# Sheet1.net
KiCad netlist of a schematic drawn in Altium Designer
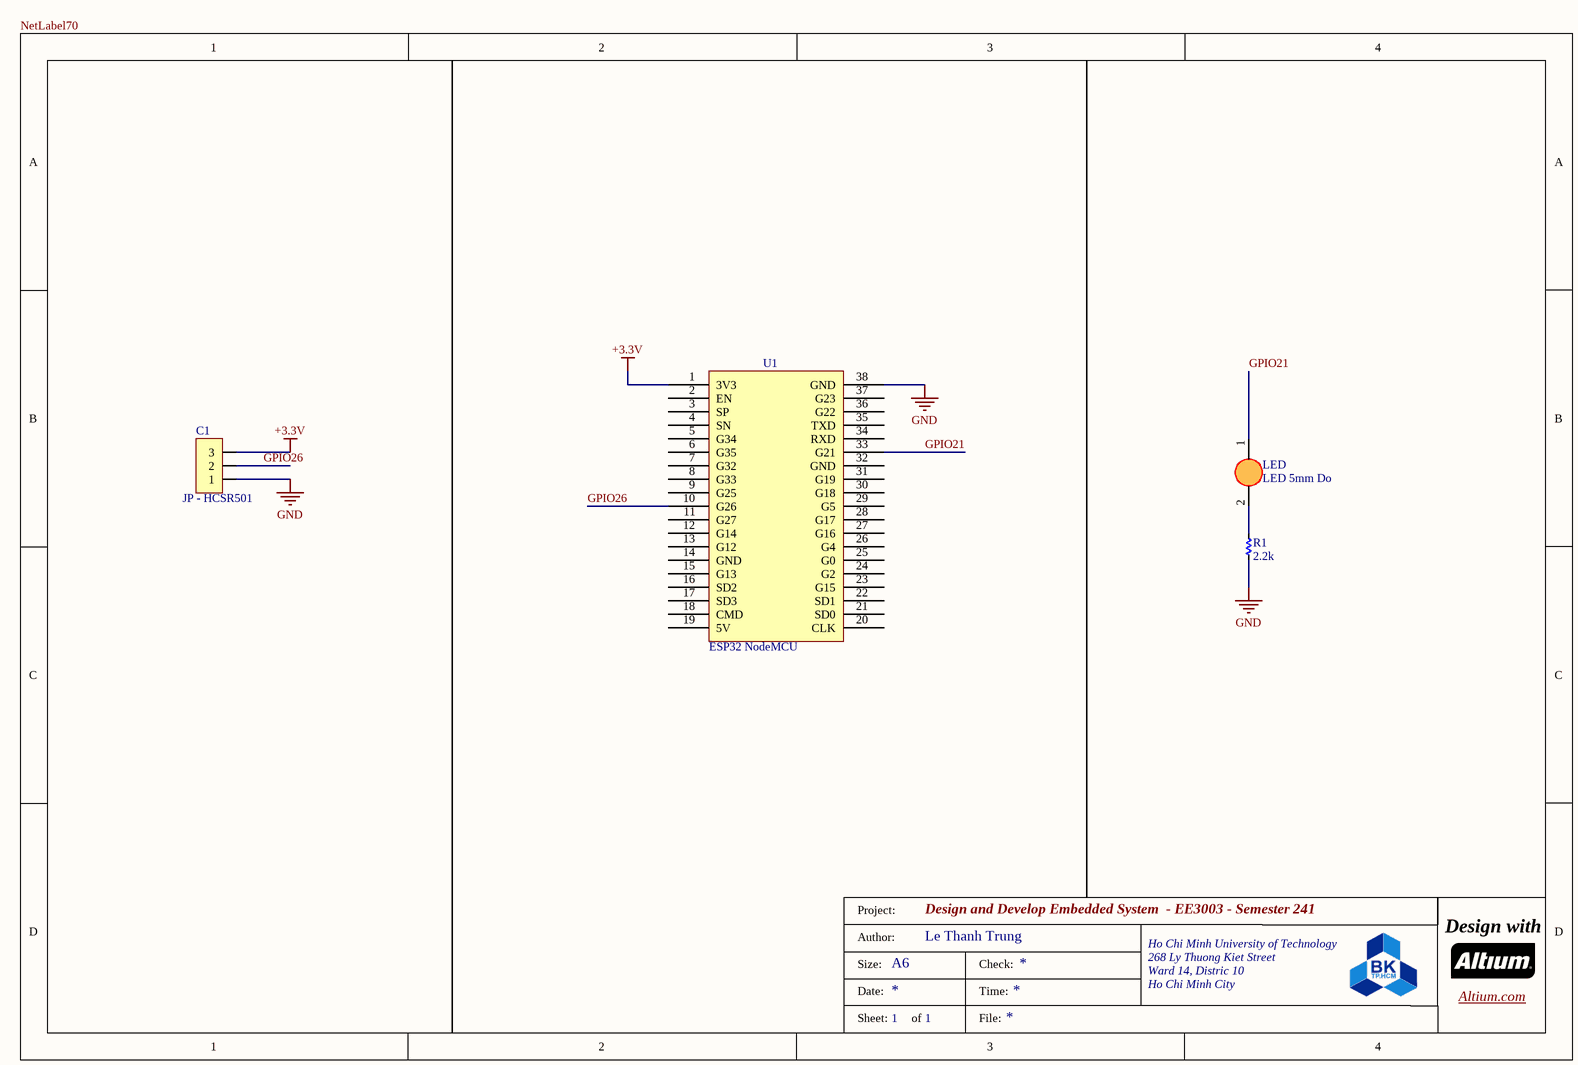
[diagram p0: Sheet1.SchDoc]

(export (version "E")
  (design (tool "Eeschema 10.0.6"))
  (components
    (comp (ref "C1")
      (value "JP - HCSR501")
      (footprint "JP3-C1T")
      (description "WR-PHD 2.54 mm Angled Socket Header")
      (fields
        (field (name "MANUFACTURER") "Würth Elektronik eiSos GmbH")
        (field (name "PARTNO") "613003143121")
        (field (name "CREATED BY") "Karrer Zheng")
      )
      (libsource (lib "KhanhBK_SCH_Library_1") (part "JP3"))
    )
    (comp (ref "LED")
      (value "LED 5mm Do")
      (footprint "LED 5mm DO")
      (description "Cắm")
      (libsource (lib "THU VIEN SCH") (part "LED 5mm Do"))
    )
    (comp (ref "R1")
      (value "2.2k")
      (footprint "RES-1W")
      (description "Res")
      (fields
        (field (name "MANUFACTURER") "Generic Components")
        (field (name "PUBLISHER") "Altium Hobart Technology Centre")
      )
      (libsource (lib "KhanhBK_SCH_Library_1") (part "Res"))
    )
    (comp (ref "U1")
      (value "ESP32 NodeMCU")
      (footprint "Nodemcu-32s")
      (description "38 pins")
      (libsource (lib "Schlib2") (part "ESP32 NodeMCU"))
    )
  )
  (nets
    (net (code "1") (name "+3.3V") (class "Default")
      (node (ref "C1") (pin "3") (pinfunction "3_3") (pintype "passive"))
      (node (ref "U1") (pin "1") (pinfunction "3V3_1") (pintype "power_in"))
    )
    (net (code "2") (name "/GPIO21") (class "Default")
      (node (ref "LED") (pin "1") (pinfunction "A_1") (pintype "passive"))
      (node (ref "U1") (pin "33") (pinfunction "G21_33") (pintype "passive"))
    )
    (net (code "3") (name "/GPIO26") (class "Default")
      (node (ref "C1") (pin "2") (pinfunction "2_2") (pintype "passive"))
      (node (ref "U1") (pin "10") (pinfunction "G26_10") (pintype "passive"))
    )
    (net (code "7") (name "GND") (class "Default")
      (node (ref "C1") (pin "1") (pinfunction "1_1") (pintype "passive"))
      (node (ref "R1") (pin "1") (pinfunction "1_1") (pintype "passive"))
      (node (ref "U1") (pin "38") (pinfunction "GND_38") (pintype "power_in"))
    )
    (net (code "8") (name "Net-(LED-K)") (class "Default")
      (node (ref "LED") (pin "2") (pinfunction "K_2") (pintype "passive"))
      (node (ref "R1") (pin "2") (pinfunction "2_2") (pintype "passive"))
    )
    (net (code "9") (name "unconnected-(U1-5V-Pad19)") (class "Default")
      (node (ref "U1") (pin "19") (pinfunction "5V_19") (pintype "power_in"))
    )
    (net (code "10") (name "unconnected-(U1-CLK-Pad20)") (class "Default")
      (node (ref "U1") (pin "20") (pinfunction "CLK_20") (pintype "passive"))
    )
    (net (code "11") (name "unconnected-(U1-CMD-Pad18)") (class "Default")
      (node (ref "U1") (pin "18") (pinfunction "CMD_18") (pintype "passive"))
    )
    (net (code "12") (name "unconnected-(U1-EN-Pad2)") (class "Default")
      (node (ref "U1") (pin "2") (pinfunction "EN_2") (pintype "passive"))
    )
    (net (code "13") (name "unconnected-(U1-G0-Pad25)") (class "Default")
      (node (ref "U1") (pin "25") (pinfunction "G0_25") (pintype "passive"))
    )
    (net (code "14") (name "unconnected-(U1-G2-Pad24)") (class "Default")
      (node (ref "U1") (pin "24") (pinfunction "G2_24") (pintype "passive"))
    )
    (net (code "15") (name "unconnected-(U1-G4-Pad26)") (class "Default")
      (node (ref "U1") (pin "26") (pinfunction "G4_26") (pintype "passive"))
    )
    (net (code "16") (name "unconnected-(U1-G5-Pad29)") (class "Default")
      (node (ref "U1") (pin "29") (pinfunction "G5_29") (pintype "passive"))
    )
    (net (code "17") (name "unconnected-(U1-G12-Pad13)") (class "Default")
      (node (ref "U1") (pin "13") (pinfunction "G12_13") (pintype "passive"))
    )
    (net (code "18") (name "unconnected-(U1-G13-Pad15)") (class "Default")
      (node (ref "U1") (pin "15") (pinfunction "G13_15") (pintype "passive"))
    )
    (net (code "19") (name "unconnected-(U1-G14-Pad12)") (class "Default")
      (node (ref "U1") (pin "12") (pinfunction "G14_12") (pintype "passive"))
    )
    (net (code "20") (name "unconnected-(U1-G15-Pad23)") (class "Default")
      (node (ref "U1") (pin "23") (pinfunction "G15_23") (pintype "passive"))
    )
    (net (code "21") (name "unconnected-(U1-G16-Pad27)") (class "Default")
      (node (ref "U1") (pin "27") (pinfunction "G16_27") (pintype "passive"))
    )
    (net (code "22") (name "unconnected-(U1-G17-Pad28)") (class "Default")
      (node (ref "U1") (pin "28") (pinfunction "G17_28") (pintype "passive"))
    )
    (net (code "23") (name "unconnected-(U1-G18-Pad30)") (class "Default")
      (node (ref "U1") (pin "30") (pinfunction "G18_30") (pintype "passive"))
    )
    (net (code "24") (name "unconnected-(U1-G19-Pad31)") (class "Default")
      (node (ref "U1") (pin "31") (pinfunction "G19_31") (pintype "passive"))
    )
    (net (code "25") (name "unconnected-(U1-G22-Pad36)") (class "Default")
      (node (ref "U1") (pin "36") (pinfunction "G22_36") (pintype "passive"))
    )
    (net (code "26") (name "unconnected-(U1-G23-Pad37)") (class "Default")
      (node (ref "U1") (pin "37") (pinfunction "G23_37") (pintype "passive"))
    )
    (net (code "27") (name "unconnected-(U1-G25-Pad9)") (class "Default")
      (node (ref "U1") (pin "9") (pinfunction "G25_9") (pintype "passive"))
    )
    (net (code "28") (name "unconnected-(U1-G27-Pad11)") (class "Default")
      (node (ref "U1") (pin "11") (pinfunction "G27_11") (pintype "passive"))
    )
    (net (code "29") (name "unconnected-(U1-G32-Pad7)") (class "Default")
      (node (ref "U1") (pin "7") (pinfunction "G32_7") (pintype "passive"))
    )
    (net (code "30") (name "unconnected-(U1-G33-Pad8)") (class "Default")
      (node (ref "U1") (pin "8") (pinfunction "G33_8") (pintype "passive"))
    )
    (net (code "31") (name "unconnected-(U1-G34-Pad5)") (class "Default")
      (node (ref "U1") (pin "5") (pinfunction "G34_5") (pintype "passive"))
    )
    (net (code "32") (name "unconnected-(U1-G35-Pad6)") (class "Default")
      (node (ref "U1") (pin "6") (pinfunction "G35_6") (pintype "passive"))
    )
    (net (code "33") (name "unconnected-(U1-GND-Pad14)") (class "Default")
      (node (ref "U1") (pin "14") (pinfunction "GND_14") (pintype "power_in"))
    )
    (net (code "34") (name "unconnected-(U1-GND-Pad32)") (class "Default")
      (node (ref "U1") (pin "32") (pinfunction "GND_32") (pintype "power_in"))
    )
    (net (code "35") (name "unconnected-(U1-RXD-Pad34)") (class "Default")
      (node (ref "U1") (pin "34") (pinfunction "RXD_34") (pintype "passive"))
    )
    (net (code "36") (name "unconnected-(U1-SD0-Pad21)") (class "Default")
      (node (ref "U1") (pin "21") (pinfunction "SD0_21") (pintype "passive"))
    )
    (net (code "37") (name "unconnected-(U1-SD1-Pad22)") (class "Default")
      (node (ref "U1") (pin "22") (pinfunction "SD1_22") (pintype "passive"))
    )
    (net (code "38") (name "unconnected-(U1-SD2-Pad16)") (class "Default")
      (node (ref "U1") (pin "16") (pinfunction "SD2_16") (pintype "passive"))
    )
    (net (code "39") (name "unconnected-(U1-SD3-Pad17)") (class "Default")
      (node (ref "U1") (pin "17") (pinfunction "SD3_17") (pintype "passive"))
    )
    (net (code "40") (name "unconnected-(U1-SN-Pad4)") (class "Default")
      (node (ref "U1") (pin "4") (pinfunction "SN_4") (pintype "passive"))
    )
    (net (code "41") (name "unconnected-(U1-SP-Pad3)") (class "Default")
      (node (ref "U1") (pin "3") (pinfunction "SP_3") (pintype "passive"))
    )
    (net (code "42") (name "unconnected-(U1-TXD-Pad35)") (class "Default")
      (node (ref "U1") (pin "35") (pinfunction "TXD_35") (pintype "passive"))
    )
  )
)
